# ver1_1.net
KiCad netlist of a schematic drawn in EAGLE
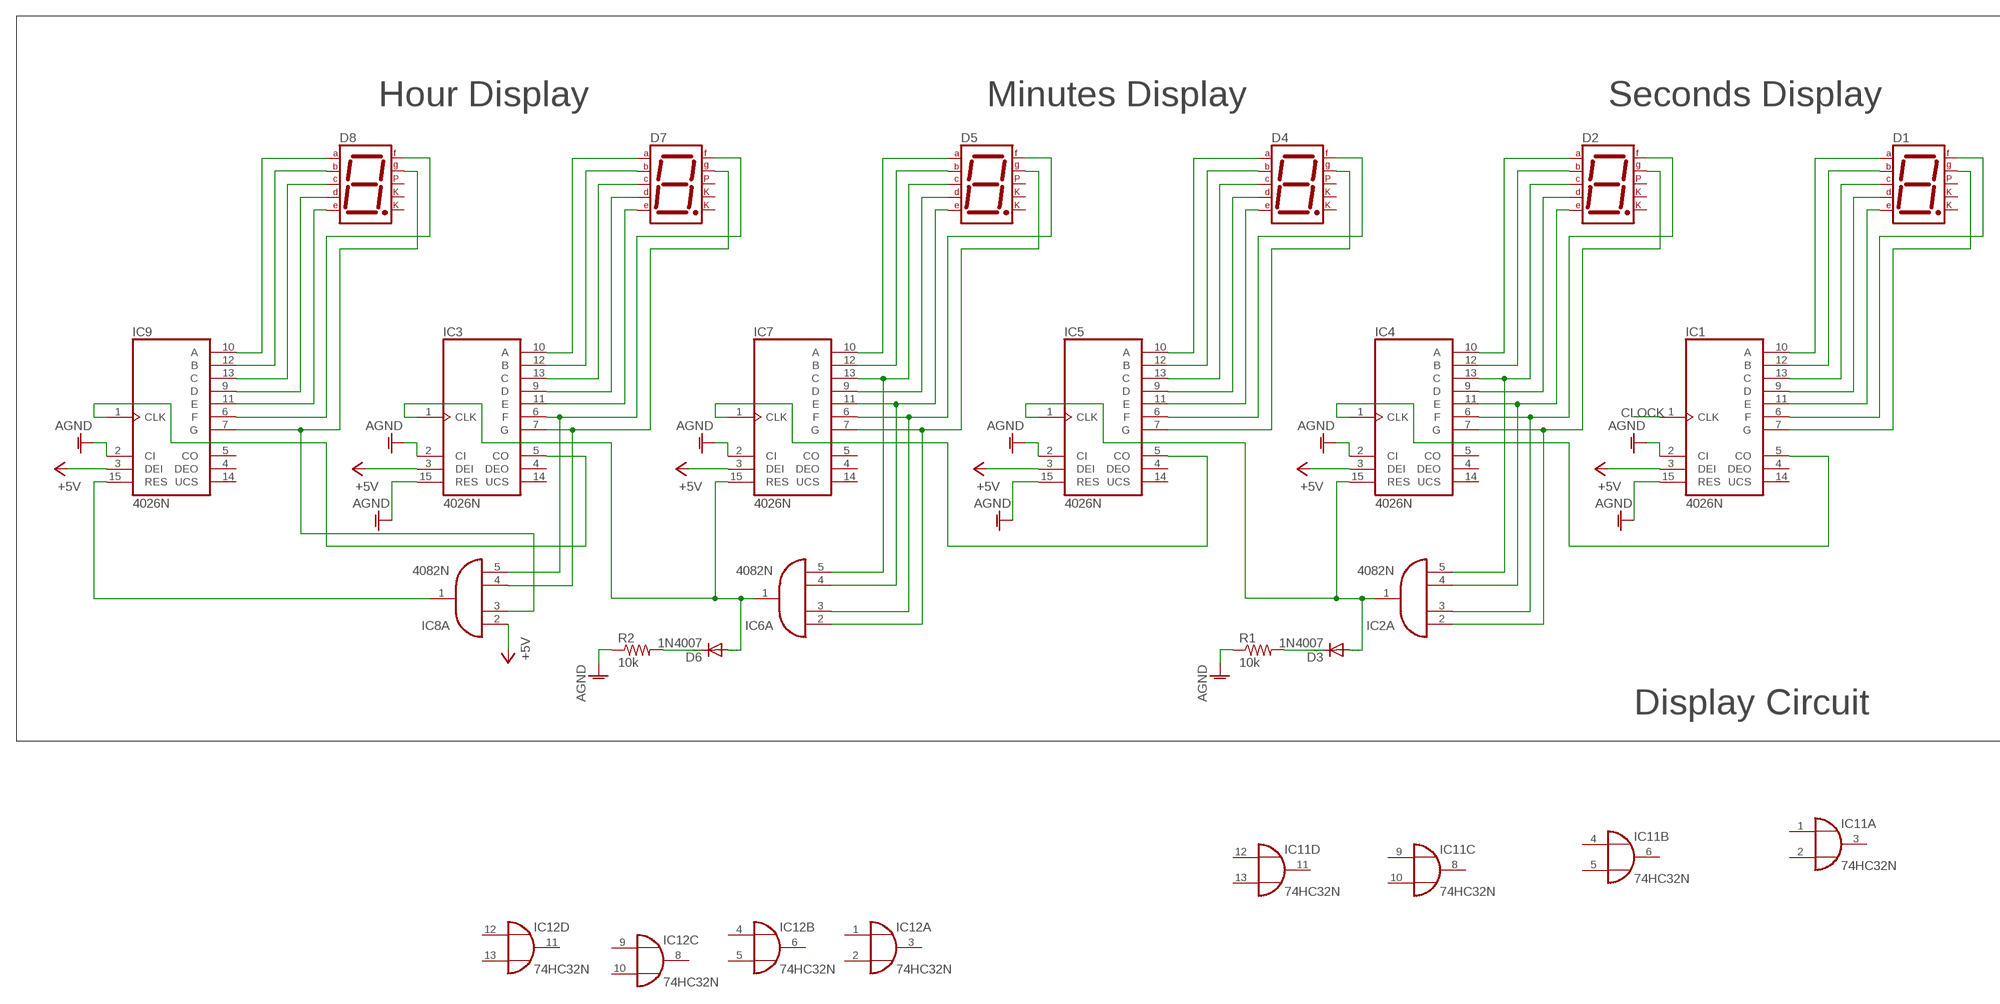
[diagram p0: schematic, sheet 1, part 1 of 2]
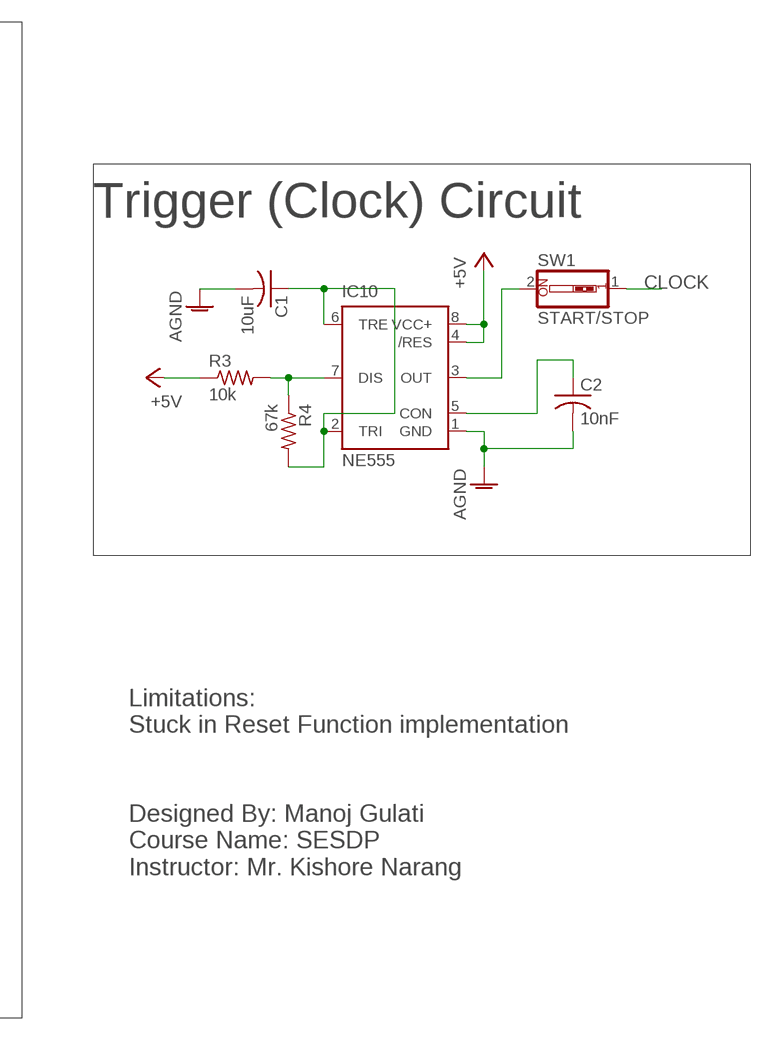
[diagram p1: schematic, sheet 1, part 2 of 2]

(export (version "E")
  (design (tool "Eeschema 10.0.6"))
  (components
    (comp (ref "C1")
      (value "10uF")
      (footprint "eagle-import:C025-024X044")
      (libsource (lib "eagle-import") (part "C-US025-024X044"))
    )
    (comp (ref "C2")
      (value "10nF")
      (footprint "eagle-import:C025-024X044")
      (libsource (lib "eagle-import") (part "C-US025-024X044"))
    )
    (comp (ref "D1")
      (value "7SEG-CK")
      (footprint "eagle-import:7SEG-13")
      (libsource (lib "eagle-import") (part "7SEG-CK"))
    )
    (comp (ref "D2")
      (value "7SEG-CK")
      (footprint "eagle-import:7SEG-13")
      (libsource (lib "eagle-import") (part "7SEG-CK"))
    )
    (comp (ref "D3")
      (value "1N4007")
      (footprint "eagle-import:DO41-10")
      (libsource (lib "eagle-import") (part "1N4004"))
    )
    (comp (ref "D4")
      (value "7SEG-CK")
      (footprint "eagle-import:7SEG-13")
      (libsource (lib "eagle-import") (part "7SEG-CK"))
    )
    (comp (ref "D5")
      (value "7SEG-CK")
      (footprint "eagle-import:7SEG-13")
      (libsource (lib "eagle-import") (part "7SEG-CK"))
    )
    (comp (ref "D6")
      (value "1N4007")
      (footprint "eagle-import:DO41-10")
      (libsource (lib "eagle-import") (part "1N4004"))
    )
    (comp (ref "D7")
      (value "7SEG-CK")
      (footprint "eagle-import:7SEG-13")
      (libsource (lib "eagle-import") (part "7SEG-CK"))
    )
    (comp (ref "D8")
      (value "7SEG-CK")
      (footprint "eagle-import:7SEG-13")
      (libsource (lib "eagle-import") (part "7SEG-CK"))
    )
    (comp (ref "IC1")
      (value "4026N")
      (footprint "eagle-import:DIL16")
      (libsource (lib "eagle-import") (part "4026N"))
    )
    (comp (ref "IC2")
      (value "4082N")
      (footprint "eagle-import:DIL14")
      (libsource (lib "eagle-import") (part "4082N"))
    )
    (comp (ref "IC3")
      (value "4026N")
      (footprint "eagle-import:DIL16")
      (libsource (lib "eagle-import") (part "4026N"))
    )
    (comp (ref "IC4")
      (value "4026N")
      (footprint "eagle-import:DIL16")
      (libsource (lib "eagle-import") (part "4026N"))
    )
    (comp (ref "IC5")
      (value "4026N")
      (footprint "eagle-import:DIL16")
      (libsource (lib "eagle-import") (part "4026N"))
    )
    (comp (ref "IC6")
      (value "4082N")
      (footprint "eagle-import:DIL14")
      (libsource (lib "eagle-import") (part "4082N"))
    )
    (comp (ref "IC7")
      (value "4026N")
      (footprint "eagle-import:DIL16")
      (libsource (lib "eagle-import") (part "4026N"))
    )
    (comp (ref "IC8")
      (value "4082N")
      (footprint "eagle-import:DIL14")
      (libsource (lib "eagle-import") (part "4082N"))
    )
    (comp (ref "IC9")
      (value "4026N")
      (footprint "eagle-import:DIL16")
      (libsource (lib "eagle-import") (part "4026N"))
    )
    (comp (ref "IC10")
      (value "NE555")
      (footprint "eagle-import:DIL-08")
      (fields (field (name "MF") "Arrow Electronics") (field (name "MPN") "NE555N"))
      (libsource (lib "eagle-import") (part "NE555"))
    )
    (comp (ref "IC11")
      (value "74HC32N")
      (footprint "eagle-import:DIL14")
      (libsource (lib "eagle-import") (part "7432NHC"))
    )
    (comp (ref "IC12")
      (value "74HC32N")
      (footprint "eagle-import:DIL14")
      (libsource (lib "eagle-import") (part "7432NHC"))
    )
    (comp (ref "R1")
      (value "10k")
      (footprint "eagle-import:0204V")
      (libsource (lib "eagle-import") (part "R-US_0204/2V"))
    )
    (comp (ref "R2")
      (value "10k")
      (footprint "eagle-import:0204V")
      (libsource (lib "eagle-import") (part "R-US_0204/2V"))
    )
    (comp (ref "R3")
      (value "10k")
      (footprint "eagle-import:0204V")
      (libsource (lib "eagle-import") (part "R-US_0204/2V"))
    )
    (comp (ref "R4")
      (value "67k")
      (footprint "eagle-import:0204V")
      (libsource (lib "eagle-import") (part "R-US_0204/2V"))
    )
    (comp (ref "SW1")
      (value "START/STOP")
      (footprint "eagle-import:EDG-01")
      (libsource (lib "eagle-import") (part "SW_DIP-1"))
    )
  )
  (nets
    (net (code "1") (name "+5V") (class "Default")
      (node (ref "IC1") (pin "3") (pinfunction "DEI_3") (pintype "input"))
      (node (ref "IC10") (pin "4") (pinfunction "/RES_4") (pintype "input"))
      (node (ref "IC10") (pin "8") (pinfunction "VCC+_8") (pintype "power_in"))
      (node (ref "IC3") (pin "3") (pinfunction "DEI_3") (pintype "input"))
      (node (ref "IC4") (pin "3") (pinfunction "DEI_3") (pintype "input"))
      (node (ref "IC5") (pin "3") (pinfunction "DEI_3") (pintype "input"))
      (node (ref "IC7") (pin "3") (pinfunction "DEI_3") (pintype "input"))
      (node (ref "IC8") (pin "2") (pinfunction "I0_2") (pintype "input"))
      (node (ref "IC9") (pin "3") (pinfunction "DEI_3") (pintype "input"))
      (node (ref "R3") (pin "1") (pinfunction "1_1") (pintype "passive"))
    )
    (net (code "2") (name "/CLOCK") (class "Default")
      (node (ref "IC1") (pin "1") (pinfunction "CLK_1") (pintype "input"))
      (node (ref "SW1") (pin "1") (pinfunction "1_1") (pintype "passive"))
    )
    (net (code "3") (name "AGND") (class "Default")
      (node (ref "C1") (pin "2") (pinfunction "2_2") (pintype "passive"))
      (node (ref "C2") (pin "2") (pinfunction "2_2") (pintype "passive"))
      (node (ref "IC1") (pin "15") (pinfunction "RES_15") (pintype "input"))
      (node (ref "IC1") (pin "2") (pinfunction "CI_2") (pintype "input"))
      (node (ref "IC10") (pin "1") (pinfunction "GND_1") (pintype "power_in"))
      (node (ref "IC3") (pin "15") (pinfunction "RES_15") (pintype "input"))
      (node (ref "IC3") (pin "2") (pinfunction "CI_2") (pintype "input"))
      (node (ref "IC4") (pin "2") (pinfunction "CI_2") (pintype "input"))
      (node (ref "IC5") (pin "15") (pinfunction "RES_15") (pintype "input"))
      (node (ref "IC5") (pin "2") (pinfunction "CI_2") (pintype "input"))
      (node (ref "IC7") (pin "2") (pinfunction "CI_2") (pintype "input"))
      (node (ref "IC9") (pin "2") (pinfunction "CI_2") (pintype "input"))
      (node (ref "R1") (pin "1") (pinfunction "1_1") (pintype "passive"))
      (node (ref "R2") (pin "1") (pinfunction "1_1") (pintype "passive"))
    )
    (net (code "4") (name "Net-(D1-A)") (class "Default")
      (node (ref "D1") (pin "7") (pinfunction "A_7") (pintype "passive"))
      (node (ref "IC1") (pin "10") (pinfunction "A_10") (pintype "output"))
    )
    (net (code "5") (name "Net-(D1-B)") (class "Default")
      (node (ref "D1") (pin "6") (pinfunction "B_6") (pintype "passive"))
      (node (ref "IC1") (pin "12") (pinfunction "B_12") (pintype "output"))
    )
    (net (code "6") (name "Net-(D1-C)") (class "Default")
      (node (ref "D1") (pin "4") (pinfunction "C_4") (pintype "passive"))
      (node (ref "IC1") (pin "13") (pinfunction "C_13") (pintype "output"))
    )
    (net (code "7") (name "Net-(D1-D)") (class "Default")
      (node (ref "D1") (pin "2") (pinfunction "D_2") (pintype "passive"))
      (node (ref "IC1") (pin "9") (pinfunction "D_9") (pintype "output"))
    )
    (net (code "8") (name "Net-(D1-E)") (class "Default")
      (node (ref "D1") (pin "1") (pinfunction "E_1") (pintype "passive"))
      (node (ref "IC1") (pin "11") (pinfunction "E_11") (pintype "output"))
    )
    (net (code "9") (name "Net-(D1-F)") (class "Default")
      (node (ref "D1") (pin "9") (pinfunction "F_9") (pintype "passive"))
      (node (ref "IC1") (pin "6") (pinfunction "F_6") (pintype "output"))
    )
    (net (code "10") (name "Net-(D1-G)") (class "Default")
      (node (ref "D1") (pin "10") (pinfunction "G_10") (pintype "passive"))
      (node (ref "IC1") (pin "7") (pinfunction "G_7") (pintype "output"))
    )
    (net (code "11") (name "Net-(D2-A)") (class "Default")
      (node (ref "D2") (pin "7") (pinfunction "A_7") (pintype "passive"))
      (node (ref "IC4") (pin "10") (pinfunction "A_10") (pintype "output"))
    )
    (net (code "12") (name "Net-(D2-B)") (class "Default")
      (node (ref "D2") (pin "6") (pinfunction "B_6") (pintype "passive"))
      (node (ref "IC4") (pin "12") (pinfunction "B_12") (pintype "output"))
    )
    (net (code "13") (name "Net-(D2-C)") (class "Default")
      (node (ref "D2") (pin "4") (pinfunction "C_4") (pintype "passive"))
      (node (ref "IC2") (pin "5") (pinfunction "I3_5") (pintype "input"))
      (node (ref "IC4") (pin "13") (pinfunction "C_13") (pintype "output"))
    )
    (net (code "14") (name "Net-(D2-D)") (class "Default")
      (node (ref "D2") (pin "2") (pinfunction "D_2") (pintype "passive"))
      (node (ref "IC4") (pin "9") (pinfunction "D_9") (pintype "output"))
    )
    (net (code "15") (name "Net-(D2-E)") (class "Default")
      (node (ref "D2") (pin "1") (pinfunction "E_1") (pintype "passive"))
      (node (ref "IC2") (pin "4") (pinfunction "I2_4") (pintype "input"))
      (node (ref "IC4") (pin "11") (pinfunction "E_11") (pintype "output"))
    )
    (net (code "16") (name "Net-(D2-F)") (class "Default")
      (node (ref "D2") (pin "9") (pinfunction "F_9") (pintype "passive"))
      (node (ref "IC2") (pin "3") (pinfunction "I1_3") (pintype "input"))
      (node (ref "IC4") (pin "6") (pinfunction "F_6") (pintype "output"))
    )
    (net (code "17") (name "Net-(D2-G)") (class "Default")
      (node (ref "D2") (pin "10") (pinfunction "G_10") (pintype "passive"))
      (node (ref "IC2") (pin "2") (pinfunction "I0_2") (pintype "input"))
      (node (ref "IC4") (pin "7") (pinfunction "G_7") (pintype "output"))
    )
    (net (code "18") (name "Net-(D3-PadC)") (class "Default")
      (node (ref "D3") (pin "C") (pinfunction "C_C") (pintype "passive"))
      (node (ref "R1") (pin "2") (pinfunction "2_2") (pintype "passive"))
    )
    (net (code "19") (name "Net-(D4-A)") (class "Default")
      (node (ref "D4") (pin "7") (pinfunction "A_7") (pintype "passive"))
      (node (ref "IC5") (pin "10") (pinfunction "A_10") (pintype "output"))
    )
    (net (code "20") (name "Net-(D4-B)") (class "Default")
      (node (ref "D4") (pin "6") (pinfunction "B_6") (pintype "passive"))
      (node (ref "IC5") (pin "12") (pinfunction "B_12") (pintype "output"))
    )
    (net (code "21") (name "Net-(D4-C)") (class "Default")
      (node (ref "D4") (pin "4") (pinfunction "C_4") (pintype "passive"))
      (node (ref "IC5") (pin "13") (pinfunction "C_13") (pintype "output"))
    )
    (net (code "22") (name "Net-(D4-D)") (class "Default")
      (node (ref "D4") (pin "2") (pinfunction "D_2") (pintype "passive"))
      (node (ref "IC5") (pin "9") (pinfunction "D_9") (pintype "output"))
    )
    (net (code "23") (name "Net-(D4-E)") (class "Default")
      (node (ref "D4") (pin "1") (pinfunction "E_1") (pintype "passive"))
      (node (ref "IC5") (pin "11") (pinfunction "E_11") (pintype "output"))
    )
    (net (code "24") (name "Net-(D4-F)") (class "Default")
      (node (ref "D4") (pin "9") (pinfunction "F_9") (pintype "passive"))
      (node (ref "IC5") (pin "6") (pinfunction "F_6") (pintype "output"))
    )
    (net (code "25") (name "Net-(D4-G)") (class "Default")
      (node (ref "D4") (pin "10") (pinfunction "G_10") (pintype "passive"))
      (node (ref "IC5") (pin "7") (pinfunction "G_7") (pintype "output"))
    )
    (net (code "26") (name "Net-(D5-A)") (class "Default")
      (node (ref "D5") (pin "7") (pinfunction "A_7") (pintype "passive"))
      (node (ref "IC7") (pin "10") (pinfunction "A_10") (pintype "output"))
    )
    (net (code "27") (name "Net-(D5-B)") (class "Default")
      (node (ref "D5") (pin "6") (pinfunction "B_6") (pintype "passive"))
      (node (ref "IC7") (pin "12") (pinfunction "B_12") (pintype "output"))
    )
    (net (code "28") (name "Net-(D5-C)") (class "Default")
      (node (ref "D5") (pin "4") (pinfunction "C_4") (pintype "passive"))
      (node (ref "IC6") (pin "5") (pinfunction "I3_5") (pintype "input"))
      (node (ref "IC7") (pin "13") (pinfunction "C_13") (pintype "output"))
    )
    (net (code "29") (name "Net-(D5-D)") (class "Default")
      (node (ref "D5") (pin "2") (pinfunction "D_2") (pintype "passive"))
      (node (ref "IC7") (pin "9") (pinfunction "D_9") (pintype "output"))
    )
    (net (code "30") (name "Net-(D5-E)") (class "Default")
      (node (ref "D5") (pin "1") (pinfunction "E_1") (pintype "passive"))
      (node (ref "IC6") (pin "4") (pinfunction "I2_4") (pintype "input"))
      (node (ref "IC7") (pin "11") (pinfunction "E_11") (pintype "output"))
    )
    (net (code "31") (name "Net-(D5-F)") (class "Default")
      (node (ref "D5") (pin "9") (pinfunction "F_9") (pintype "passive"))
      (node (ref "IC6") (pin "3") (pinfunction "I1_3") (pintype "input"))
      (node (ref "IC7") (pin "6") (pinfunction "F_6") (pintype "output"))
    )
    (net (code "32") (name "Net-(D5-G)") (class "Default")
      (node (ref "D5") (pin "10") (pinfunction "G_10") (pintype "passive"))
      (node (ref "IC6") (pin "2") (pinfunction "I0_2") (pintype "input"))
      (node (ref "IC7") (pin "7") (pinfunction "G_7") (pintype "output"))
    )
    (net (code "33") (name "Net-(D6-PadC)") (class "Default")
      (node (ref "D6") (pin "C") (pinfunction "C_C") (pintype "passive"))
      (node (ref "R2") (pin "2") (pinfunction "2_2") (pintype "passive"))
    )
    (net (code "34") (name "Net-(D7-A)") (class "Default")
      (node (ref "D7") (pin "7") (pinfunction "A_7") (pintype "passive"))
      (node (ref "IC3") (pin "10") (pinfunction "A_10") (pintype "output"))
    )
    (net (code "35") (name "Net-(D7-B)") (class "Default")
      (node (ref "D7") (pin "6") (pinfunction "B_6") (pintype "passive"))
      (node (ref "IC3") (pin "12") (pinfunction "B_12") (pintype "output"))
    )
    (net (code "36") (name "Net-(D7-C)") (class "Default")
      (node (ref "D7") (pin "4") (pinfunction "C_4") (pintype "passive"))
      (node (ref "IC3") (pin "13") (pinfunction "C_13") (pintype "output"))
    )
    (net (code "37") (name "Net-(D7-D)") (class "Default")
      (node (ref "D7") (pin "2") (pinfunction "D_2") (pintype "passive"))
      (node (ref "IC3") (pin "9") (pinfunction "D_9") (pintype "output"))
    )
    (net (code "38") (name "Net-(D7-E)") (class "Default")
      (node (ref "D7") (pin "1") (pinfunction "E_1") (pintype "passive"))
      (node (ref "IC3") (pin "11") (pinfunction "E_11") (pintype "output"))
    )
    (net (code "39") (name "Net-(D7-F)") (class "Default")
      (node (ref "D7") (pin "10") (pinfunction "G_10") (pintype "passive"))
      (node (ref "D7") (pin "9") (pinfunction "F_9") (pintype "passive"))
      (node (ref "IC3") (pin "6") (pinfunction "F_6") (pintype "output"))
      (node (ref "IC3") (pin "7") (pinfunction "G_7") (pintype "output"))
      (node (ref "IC8") (pin "4") (pinfunction "I2_4") (pintype "input"))
      (node (ref "IC8") (pin "5") (pinfunction "I3_5") (pintype "input"))
    )
    (net (code "40") (name "Net-(D8-A)") (class "Default")
      (node (ref "D8") (pin "7") (pinfunction "A_7") (pintype "passive"))
      (node (ref "IC9") (pin "10") (pinfunction "A_10") (pintype "output"))
    )
    (net (code "41") (name "Net-(D8-B)") (class "Default")
      (node (ref "D8") (pin "6") (pinfunction "B_6") (pintype "passive"))
      (node (ref "IC9") (pin "12") (pinfunction "B_12") (pintype "output"))
    )
    (net (code "42") (name "Net-(D8-C)") (class "Default")
      (node (ref "D8") (pin "4") (pinfunction "C_4") (pintype "passive"))
      (node (ref "IC9") (pin "13") (pinfunction "C_13") (pintype "output"))
    )
    (net (code "43") (name "Net-(D8-D)") (class "Default")
      (node (ref "D8") (pin "2") (pinfunction "D_2") (pintype "passive"))
      (node (ref "IC9") (pin "9") (pinfunction "D_9") (pintype "output"))
    )
    (net (code "44") (name "Net-(D8-E)") (class "Default")
      (node (ref "D8") (pin "1") (pinfunction "E_1") (pintype "passive"))
      (node (ref "IC9") (pin "11") (pinfunction "E_11") (pintype "output"))
    )
    (net (code "45") (name "Net-(D8-F)") (class "Default")
      (node (ref "D8") (pin "9") (pinfunction "F_9") (pintype "passive"))
      (node (ref "IC9") (pin "6") (pinfunction "F_6") (pintype "output"))
    )
    (net (code "46") (name "Net-(D8-G)") (class "Default")
      (node (ref "D8") (pin "10") (pinfunction "G_10") (pintype "passive"))
      (node (ref "IC8") (pin "3") (pinfunction "I1_3") (pintype "input"))
      (node (ref "IC9") (pin "7") (pinfunction "G_7") (pintype "output"))
    )
    (net (code "47") (name "Net-(IC1A-CO)") (class "Default")
      (node (ref "IC1") (pin "5") (pinfunction "CO_5") (pintype "output"))
      (node (ref "IC4") (pin "1") (pinfunction "CLK_1") (pintype "input"))
    )
    (net (code "48") (name "Net-(IC2A-O)") (class "Default")
      (node (ref "D3") (pin "A") (pinfunction "A_A") (pintype "passive"))
      (node (ref "IC2") (pin "1") (pinfunction "O_1") (pintype "output"))
      (node (ref "IC4") (pin "15") (pinfunction "RES_15") (pintype "input"))
      (node (ref "IC5") (pin "1") (pinfunction "CLK_1") (pintype "input"))
    )
    (net (code "49") (name "Net-(IC3A-CLK)") (class "Default")
      (node (ref "D6") (pin "A") (pinfunction "A_A") (pintype "passive"))
      (node (ref "IC3") (pin "1") (pinfunction "CLK_1") (pintype "input"))
      (node (ref "IC6") (pin "1") (pinfunction "O_1") (pintype "output"))
      (node (ref "IC7") (pin "15") (pinfunction "RES_15") (pintype "input"))
    )
    (net (code "50") (name "Net-(IC3A-CO)") (class "Default")
      (node (ref "IC3") (pin "5") (pinfunction "CO_5") (pintype "output"))
      (node (ref "IC9") (pin "1") (pinfunction "CLK_1") (pintype "input"))
    )
    (net (code "51") (name "Net-(IC5A-CO)") (class "Default")
      (node (ref "IC5") (pin "5") (pinfunction "CO_5") (pintype "output"))
      (node (ref "IC7") (pin "1") (pinfunction "CLK_1") (pintype "input"))
    )
    (net (code "52") (name "Net-(IC8A-O)") (class "Default")
      (node (ref "IC8") (pin "1") (pinfunction "O_1") (pintype "output"))
      (node (ref "IC9") (pin "15") (pinfunction "RES_15") (pintype "input"))
    )
    (net (code "53") (name "Net-(IC10-CON)") (class "Default")
      (node (ref "C2") (pin "1") (pinfunction "1_1") (pintype "passive"))
      (node (ref "IC10") (pin "5") (pinfunction "CON_5") (pintype "input"))
    )
    (net (code "54") (name "Net-(IC10-DIS)") (class "Default")
      (node (ref "IC10") (pin "7") (pinfunction "DIS_7") (pintype "input"))
      (node (ref "R3") (pin "2") (pinfunction "2_2") (pintype "passive"))
      (node (ref "R4") (pin "1") (pinfunction "1_1") (pintype "passive"))
    )
    (net (code "55") (name "Net-(IC10-OUT)") (class "Default")
      (node (ref "IC10") (pin "3") (pinfunction "OUT_3") (pintype "output"))
      (node (ref "SW1") (pin "2") (pinfunction "2_2") (pintype "passive"))
    )
    (net (code "56") (name "Net-(IC10-TRE)") (class "Default")
      (node (ref "C1") (pin "1") (pinfunction "1_1") (pintype "passive"))
      (node (ref "IC10") (pin "2") (pinfunction "TRI_2") (pintype "input"))
      (node (ref "IC10") (pin "6") (pinfunction "TRE_6") (pintype "input"))
      (node (ref "R4") (pin "2") (pinfunction "2_2") (pintype "passive"))
    )
    (net (code "57") (name "unconnected-(D1-CK1-Pad3)") (class "Default")
      (node (ref "D1") (pin "3") (pinfunction "CK1_3") (pintype "passive"))
    )
    (net (code "58") (name "unconnected-(D1-CK2-Pad8)") (class "Default")
      (node (ref "D1") (pin "8") (pinfunction "CK2_8") (pintype "passive"))
    )
    (net (code "59") (name "unconnected-(D1-DP-Pad5)") (class "Default")
      (node (ref "D1") (pin "5") (pinfunction "DP_5") (pintype "passive"))
    )
    (net (code "60") (name "unconnected-(D2-CK1-Pad3)") (class "Default")
      (node (ref "D2") (pin "3") (pinfunction "CK1_3") (pintype "passive"))
    )
    (net (code "61") (name "unconnected-(D2-CK2-Pad8)") (class "Default")
      (node (ref "D2") (pin "8") (pinfunction "CK2_8") (pintype "passive"))
    )
    (net (code "62") (name "unconnected-(D2-DP-Pad5)") (class "Default")
      (node (ref "D2") (pin "5") (pinfunction "DP_5") (pintype "passive"))
    )
    (net (code "63") (name "unconnected-(D4-CK1-Pad3)") (class "Default")
      (node (ref "D4") (pin "3") (pinfunction "CK1_3") (pintype "passive"))
    )
    (net (code "64") (name "unconnected-(D4-CK2-Pad8)") (class "Default")
      (node (ref "D4") (pin "8") (pinfunction "CK2_8") (pintype "passive"))
    )
    (net (code "65") (name "unconnected-(D4-DP-Pad5)") (class "Default")
      (node (ref "D4") (pin "5") (pinfunction "DP_5") (pintype "passive"))
    )
    (net (code "66") (name "unconnected-(D5-CK1-Pad3)") (class "Default")
      (node (ref "D5") (pin "3") (pinfunction "CK1_3") (pintype "passive"))
    )
    (net (code "67") (name "unconnected-(D5-CK2-Pad8)") (class "Default")
      (node (ref "D5") (pin "8") (pinfunction "CK2_8") (pintype "passive"))
    )
    (net (code "68") (name "unconnected-(D5-DP-Pad5)") (class "Default")
      (node (ref "D5") (pin "5") (pinfunction "DP_5") (pintype "passive"))
    )
    (net (code "69") (name "unconnected-(D7-CK1-Pad3)") (class "Default")
      (node (ref "D7") (pin "3") (pinfunction "CK1_3") (pintype "passive"))
    )
    (net (code "70") (name "unconnected-(D7-CK2-Pad8)") (class "Default")
      (node (ref "D7") (pin "8") (pinfunction "CK2_8") (pintype "passive"))
    )
    (net (code "71") (name "unconnected-(D7-DP-Pad5)") (class "Default")
      (node (ref "D7") (pin "5") (pinfunction "DP_5") (pintype "passive"))
    )
    (net (code "72") (name "unconnected-(D8-CK1-Pad3)") (class "Default")
      (node (ref "D8") (pin "3") (pinfunction "CK1_3") (pintype "passive"))
    )
    (net (code "73") (name "unconnected-(D8-CK2-Pad8)") (class "Default")
      (node (ref "D8") (pin "8") (pinfunction "CK2_8") (pintype "passive"))
    )
    (net (code "74") (name "unconnected-(D8-DP-Pad5)") (class "Default")
      (node (ref "D8") (pin "5") (pinfunction "DP_5") (pintype "passive"))
    )
    (net (code "75") (name "unconnected-(IC1A-DEO-Pad4)") (class "Default")
      (node (ref "IC1") (pin "4") (pinfunction "DEO_4") (pintype "output"))
    )
    (net (code "76") (name "unconnected-(IC1A-UCS-Pad14)") (class "Default")
      (node (ref "IC1") (pin "14") (pinfunction "UCS_14") (pintype "output"))
    )
    (net (code "77") (name "unconnected-(IC3A-DEO-Pad4)") (class "Default")
      (node (ref "IC3") (pin "4") (pinfunction "DEO_4") (pintype "output"))
    )
    (net (code "78") (name "unconnected-(IC3A-UCS-Pad14)") (class "Default")
      (node (ref "IC3") (pin "14") (pinfunction "UCS_14") (pintype "output"))
    )
    (net (code "79") (name "unconnected-(IC4A-CO-Pad5)") (class "Default")
      (node (ref "IC4") (pin "5") (pinfunction "CO_5") (pintype "output"))
    )
    (net (code "80") (name "unconnected-(IC4A-DEO-Pad4)") (class "Default")
      (node (ref "IC4") (pin "4") (pinfunction "DEO_4") (pintype "output"))
    )
    (net (code "81") (name "unconnected-(IC4A-UCS-Pad14)") (class "Default")
      (node (ref "IC4") (pin "14") (pinfunction "UCS_14") (pintype "output"))
    )
    (net (code "82") (name "unconnected-(IC5A-DEO-Pad4)") (class "Default")
      (node (ref "IC5") (pin "4") (pinfunction "DEO_4") (pintype "output"))
    )
    (net (code "83") (name "unconnected-(IC5A-UCS-Pad14)") (class "Default")
      (node (ref "IC5") (pin "14") (pinfunction "UCS_14") (pintype "output"))
    )
    (net (code "84") (name "unconnected-(IC7A-CO-Pad5)") (class "Default")
      (node (ref "IC7") (pin "5") (pinfunction "CO_5") (pintype "output"))
    )
    (net (code "85") (name "unconnected-(IC7A-DEO-Pad4)") (class "Default")
      (node (ref "IC7") (pin "4") (pinfunction "DEO_4") (pintype "output"))
    )
    (net (code "86") (name "unconnected-(IC7A-UCS-Pad14)") (class "Default")
      (node (ref "IC7") (pin "14") (pinfunction "UCS_14") (pintype "output"))
    )
    (net (code "87") (name "unconnected-(IC9A-CO-Pad5)") (class "Default")
      (node (ref "IC9") (pin "5") (pinfunction "CO_5") (pintype "output"))
    )
    (net (code "88") (name "unconnected-(IC9A-DEO-Pad4)") (class "Default")
      (node (ref "IC9") (pin "4") (pinfunction "DEO_4") (pintype "output"))
    )
    (net (code "89") (name "unconnected-(IC9A-UCS-Pad14)") (class "Default")
      (node (ref "IC9") (pin "14") (pinfunction "UCS_14") (pintype "output"))
    )
    (net (code "90") (name "unconnected-(IC11A-I0-Pad1)") (class "Default")
      (node (ref "IC11") (pin "1") (pinfunction "I0_1") (pintype "input"))
    )
    (net (code "91") (name "unconnected-(IC11A-I1-Pad2)") (class "Default")
      (node (ref "IC11") (pin "2") (pinfunction "I1_2") (pintype "input"))
    )
    (net (code "92") (name "unconnected-(IC11A-O-Pad3)") (class "Default")
      (node (ref "IC11") (pin "3") (pinfunction "O_3") (pintype "output"))
    )
    (net (code "93") (name "unconnected-(IC11B-I0-Pad4)") (class "Default")
      (node (ref "IC11") (pin "4") (pinfunction "I0_4") (pintype "input"))
    )
    (net (code "94") (name "unconnected-(IC11B-I1-Pad5)") (class "Default")
      (node (ref "IC11") (pin "5") (pinfunction "I1_5") (pintype "input"))
    )
    (net (code "95") (name "unconnected-(IC11B-O-Pad6)") (class "Default")
      (node (ref "IC11") (pin "6") (pinfunction "O_6") (pintype "output"))
    )
    (net (code "96") (name "unconnected-(IC11C-I0-Pad9)") (class "Default")
      (node (ref "IC11") (pin "9") (pinfunction "I0_9") (pintype "input"))
    )
    (net (code "97") (name "unconnected-(IC11C-I1-Pad10)") (class "Default")
      (node (ref "IC11") (pin "10") (pinfunction "I1_10") (pintype "input"))
    )
    (net (code "98") (name "unconnected-(IC11C-O-Pad8)") (class "Default")
      (node (ref "IC11") (pin "8") (pinfunction "O_8") (pintype "output"))
    )
    (net (code "99") (name "unconnected-(IC11D-I0-Pad12)") (class "Default")
      (node (ref "IC11") (pin "12") (pinfunction "I0_12") (pintype "input"))
    )
    (net (code "100") (name "unconnected-(IC11D-I1-Pad13)") (class "Default")
      (node (ref "IC11") (pin "13") (pinfunction "I1_13") (pintype "input"))
    )
    (net (code "101") (name "unconnected-(IC11D-O-Pad11)") (class "Default")
      (node (ref "IC11") (pin "11") (pinfunction "O_11") (pintype "output"))
    )
    (net (code "102") (name "unconnected-(IC12A-I0-Pad1)") (class "Default")
      (node (ref "IC12") (pin "1") (pinfunction "I0_1") (pintype "input"))
    )
    (net (code "103") (name "unconnected-(IC12A-I1-Pad2)") (class "Default")
      (node (ref "IC12") (pin "2") (pinfunction "I1_2") (pintype "input"))
    )
    (net (code "104") (name "unconnected-(IC12A-O-Pad3)") (class "Default")
      (node (ref "IC12") (pin "3") (pinfunction "O_3") (pintype "output"))
    )
    (net (code "105") (name "unconnected-(IC12B-I0-Pad4)") (class "Default")
      (node (ref "IC12") (pin "4") (pinfunction "I0_4") (pintype "input"))
    )
    (net (code "106") (name "unconnected-(IC12B-I1-Pad5)") (class "Default")
      (node (ref "IC12") (pin "5") (pinfunction "I1_5") (pintype "input"))
    )
    (net (code "107") (name "unconnected-(IC12B-O-Pad6)") (class "Default")
      (node (ref "IC12") (pin "6") (pinfunction "O_6") (pintype "output"))
    )
    (net (code "108") (name "unconnected-(IC12C-I0-Pad9)") (class "Default")
      (node (ref "IC12") (pin "9") (pinfunction "I0_9") (pintype "input"))
    )
    (net (code "109") (name "unconnected-(IC12C-I1-Pad10)") (class "Default")
      (node (ref "IC12") (pin "10") (pinfunction "I1_10") (pintype "input"))
    )
    (net (code "110") (name "unconnected-(IC12C-O-Pad8)") (class "Default")
      (node (ref "IC12") (pin "8") (pinfunction "O_8") (pintype "output"))
    )
    (net (code "111") (name "unconnected-(IC12D-I0-Pad12)") (class "Default")
      (node (ref "IC12") (pin "12") (pinfunction "I0_12") (pintype "input"))
    )
    (net (code "112") (name "unconnected-(IC12D-I1-Pad13)") (class "Default")
      (node (ref "IC12") (pin "13") (pinfunction "I1_13") (pintype "input"))
    )
    (net (code "113") (name "unconnected-(IC12D-O-Pad11)") (class "Default")
      (node (ref "IC12") (pin "11") (pinfunction "O_11") (pintype "output"))
    )
  )
)
